# camera.net
KiCad netlist of a schematic drawn in Altium Designer
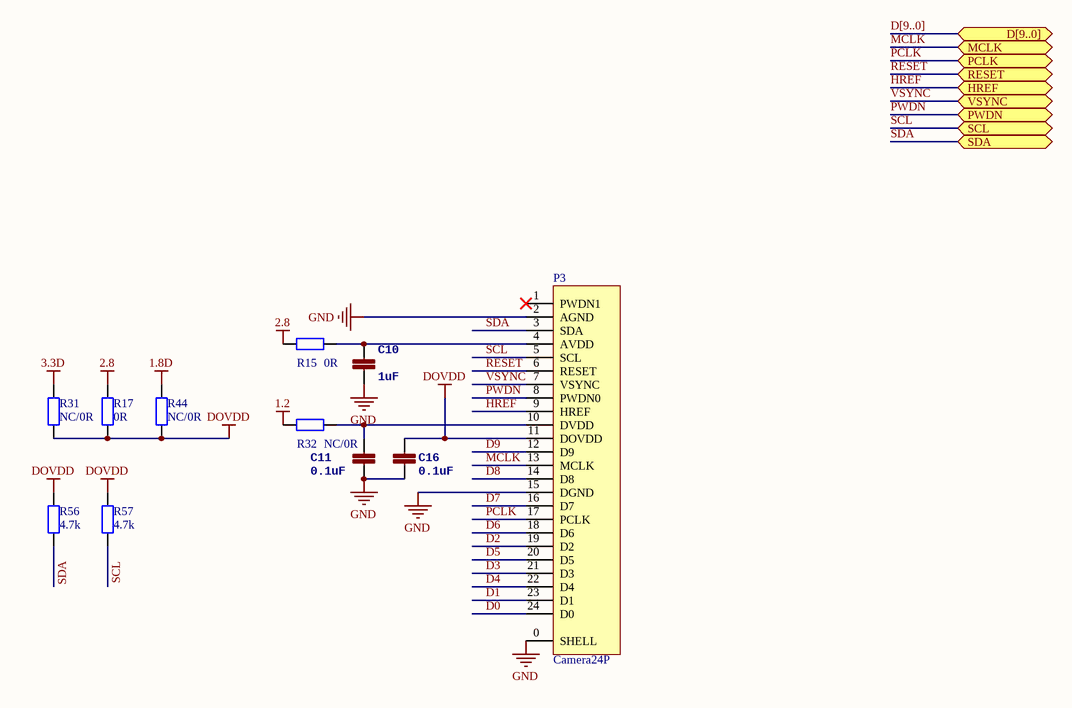
[diagram p0: camera.SchDoc]

(export (version "E")
  (design (tool "Eeschema 10.0.6"))
  (components
    (comp (ref "C10")
      (value "1uF")
      (footprint "0402")
      (description "<b>Capacitor</b>\nStandard 0603 ceramic capacitor, and 0.1\" leaded capacitor.")
      (fields (field (name "PARTNO") "CC0402ZRY5V7BB104"))
      (libsource (lib "pixhawk2") (part "CAP0402-CAP"))
    )
    (comp (ref "C11")
      (value "0.1uF")
      (footprint "0402")
      (description "<b>Capacitor</b>\nStandard 0603 ceramic capacitor, and 0.1\" leaded capacitor.")
      (fields (field (name "PARTNO") "CC0402ZRY5V7BB104"))
      (libsource (lib "pixhawk2") (part "CAP0402-CAP"))
    )
    (comp (ref "C16")
      (value "0.1uF")
      (footprint "0402")
      (description "<b>Capacitor</b>\nStandard 0603 ceramic capacitor, and 0.1\" leaded capacitor.")
      (fields (field (name "PARTNO") "CC0402ZRY5V7BB104"))
      (libsource (lib "pixhawk2") (part "CAP0402-CAP"))
    )
    (comp (ref "P3")
      (value "Camera24P")
      (footprint "FPC-0.5mm-24")
      (libsource (lib "sch") (part "Camera24P"))
    )
    (comp (ref "R15")
      (value "0R")
      (footprint "0402")
      (description "Resistor")
      (fields (field (name "PUBLISHER") "Altium Limited"))
      (libsource (lib "") (part "Res2_1"))
    )
    (comp (ref "R17")
      (value "0R")
      (footprint "0402")
      (description "Resistor")
      (fields (field (name "PUBLISHER") "Altium Limited"))
      (libsource (lib "Miscellaneous Devices") (part "Res2"))
    )
    (comp (ref "R31")
      (value "NC/0R")
      (footprint "0402")
      (description "Resistor")
      (fields (field (name "PUBLISHER") "Altium Limited"))
      (libsource (lib "Miscellaneous Devices") (part "Res2"))
    )
    (comp (ref "R32")
      (value "NC/0R")
      (footprint "0402")
      (description "Resistor")
      (fields (field (name "PUBLISHER") "Altium Limited"))
      (libsource (lib "") (part "Res2_1"))
    )
    (comp (ref "R44")
      (value "NC/0R")
      (footprint "0402")
      (description "Resistor")
      (fields (field (name "PUBLISHER") "Altium Limited"))
      (libsource (lib "Miscellaneous Devices") (part "Res2"))
    )
    (comp (ref "R56")
      (value "4.7k")
      (footprint "0402")
      (description "Resistor")
      (fields (field (name "PUBLISHER") "Altium Limited"))
      (libsource (lib "Miscellaneous Devices") (part "Res2"))
    )
    (comp (ref "R57")
      (value "4.7k")
      (footprint "0402")
      (description "Resistor")
      (fields (field (name "PUBLISHER") "Altium Limited"))
      (libsource (lib "Miscellaneous Devices") (part "Res2"))
    )
  )
  (nets
    (net (code "1") (name "/D0") (class "Default")
      (node (ref "P3") (pin "24") (pinfunction "D0_24") (pintype "passive"))
    )
    (net (code "2") (name "/D1") (class "Default")
      (node (ref "P3") (pin "23") (pinfunction "D1_23") (pintype "passive"))
    )
    (net (code "3") (name "/D2") (class "Default")
      (node (ref "P3") (pin "19") (pinfunction "D2_19") (pintype "passive"))
    )
    (net (code "4") (name "/D3") (class "Default")
      (node (ref "P3") (pin "21") (pinfunction "D3_21") (pintype "passive"))
    )
    (net (code "5") (name "/D4") (class "Default")
      (node (ref "P3") (pin "22") (pinfunction "D4_22") (pintype "passive"))
    )
    (net (code "6") (name "/D5") (class "Default")
      (node (ref "P3") (pin "20") (pinfunction "D5_20") (pintype "passive"))
    )
    (net (code "7") (name "/D6") (class "Default")
      (node (ref "P3") (pin "18") (pinfunction "D6_18") (pintype "passive"))
    )
    (net (code "8") (name "/D7") (class "Default")
      (node (ref "P3") (pin "16") (pinfunction "D7_16") (pintype "passive"))
    )
    (net (code "9") (name "/D8") (class "Default")
      (node (ref "P3") (pin "14") (pinfunction "D8_14") (pintype "passive"))
    )
    (net (code "10") (name "/D9") (class "Default")
      (node (ref "P3") (pin "12") (pinfunction "D9_12") (pintype "passive"))
    )
    (net (code "12") (name "/HREF") (class "Default")
      (node (ref "P3") (pin "9") (pinfunction "HREF_9") (pintype "passive"))
    )
    (net (code "13") (name "/MCLK") (class "Default")
      (node (ref "P3") (pin "13") (pinfunction "MCLK_13") (pintype "passive"))
    )
    (net (code "14") (name "/PCLK") (class "Default")
      (node (ref "P3") (pin "17") (pinfunction "PCLK_17") (pintype "passive"))
    )
    (net (code "15") (name "/PWDN") (class "Default")
      (node (ref "P3") (pin "8") (pinfunction "PWDN0_8") (pintype "passive"))
    )
    (net (code "16") (name "/RESET") (class "Default")
      (node (ref "P3") (pin "6") (pinfunction "RESET_6") (pintype "passive"))
    )
    (net (code "17") (name "/SCL") (class "Default")
      (node (ref "P3") (pin "5") (pinfunction "SCL_5") (pintype "passive"))
      (node (ref "R57") (pin "2") (pinfunction "2_2") (pintype "passive"))
    )
    (net (code "18") (name "/SDA") (class "Default")
      (node (ref "P3") (pin "3") (pinfunction "SDA_3") (pintype "passive"))
      (node (ref "R56") (pin "2") (pinfunction "2_2") (pintype "passive"))
    )
    (net (code "19") (name "/VSYNC") (class "Default")
      (node (ref "P3") (pin "7") (pinfunction "VSYNC_7") (pintype "passive"))
    )
    (net (code "20") (name "1.2") (class "Default")
      (node (ref "R32") (pin "2") (pinfunction "2_2") (pintype "passive"))
    )
    (net (code "21") (name "1.8D") (class "Default")
      (node (ref "R44") (pin "1") (pinfunction "1_1") (pintype "passive"))
    )
    (net (code "22") (name "2.8") (class "Default")
      (node (ref "R15") (pin "2") (pinfunction "2_2") (pintype "passive"))
      (node (ref "R17") (pin "1") (pinfunction "1_1") (pintype "passive"))
    )
    (net (code "23") (name "3.3D") (class "Default")
      (node (ref "R31") (pin "1") (pinfunction "1_1") (pintype "passive"))
    )
    (net (code "24") (name "DOVDD") (class "Default")
      (node (ref "C16") (pin "2") (pinfunction "2_2") (pintype "passive"))
      (node (ref "P3") (pin "11") (pinfunction "DOVDD_11") (pintype "passive"))
      (node (ref "R17") (pin "2") (pinfunction "2_2") (pintype "passive"))
      (node (ref "R31") (pin "2") (pinfunction "2_2") (pintype "passive"))
      (node (ref "R44") (pin "2") (pinfunction "2_2") (pintype "passive"))
      (node (ref "R56") (pin "1") (pinfunction "1_1") (pintype "passive"))
      (node (ref "R57") (pin "1") (pinfunction "1_1") (pintype "passive"))
    )
    (net (code "25") (name "GND") (class "Default")
      (node (ref "C10") (pin "1") (pinfunction "1_1") (pintype "passive"))
      (node (ref "C11") (pin "1") (pinfunction "1_1") (pintype "passive"))
      (node (ref "C16") (pin "1") (pinfunction "1_1") (pintype "passive"))
      (node (ref "P3") (pin "0") (pinfunction "SHELL_0") (pintype "passive"))
      (node (ref "P3") (pin "15") (pinfunction "DGND_15") (pintype "passive"))
      (node (ref "P3") (pin "2") (pinfunction "AGND_2") (pintype "passive"))
    )
    (net (code "26") (name "Net-(P3-AVDD)") (class "Default")
      (node (ref "C10") (pin "2") (pinfunction "2_2") (pintype "passive"))
      (node (ref "P3") (pin "4") (pinfunction "AVDD_4") (pintype "passive"))
      (node (ref "R15") (pin "1") (pinfunction "1_1") (pintype "passive"))
    )
    (net (code "27") (name "Net-(P3-DVDD)") (class "Default")
      (node (ref "C11") (pin "2") (pinfunction "2_2") (pintype "passive"))
      (node (ref "P3") (pin "10") (pinfunction "DVDD_10") (pintype "passive"))
      (node (ref "R32") (pin "1") (pinfunction "1_1") (pintype "passive"))
    )
    (net (code "28") (name "unconnected-(P3-PWDN1-Pad1)") (class "Default")
      (node (ref "P3") (pin "1") (pinfunction "PWDN1_1") (pintype "passive+no_connect"))
    )
  )
)
